# Group_02.net
KiCad netlist of a schematic drawn in EAGLE
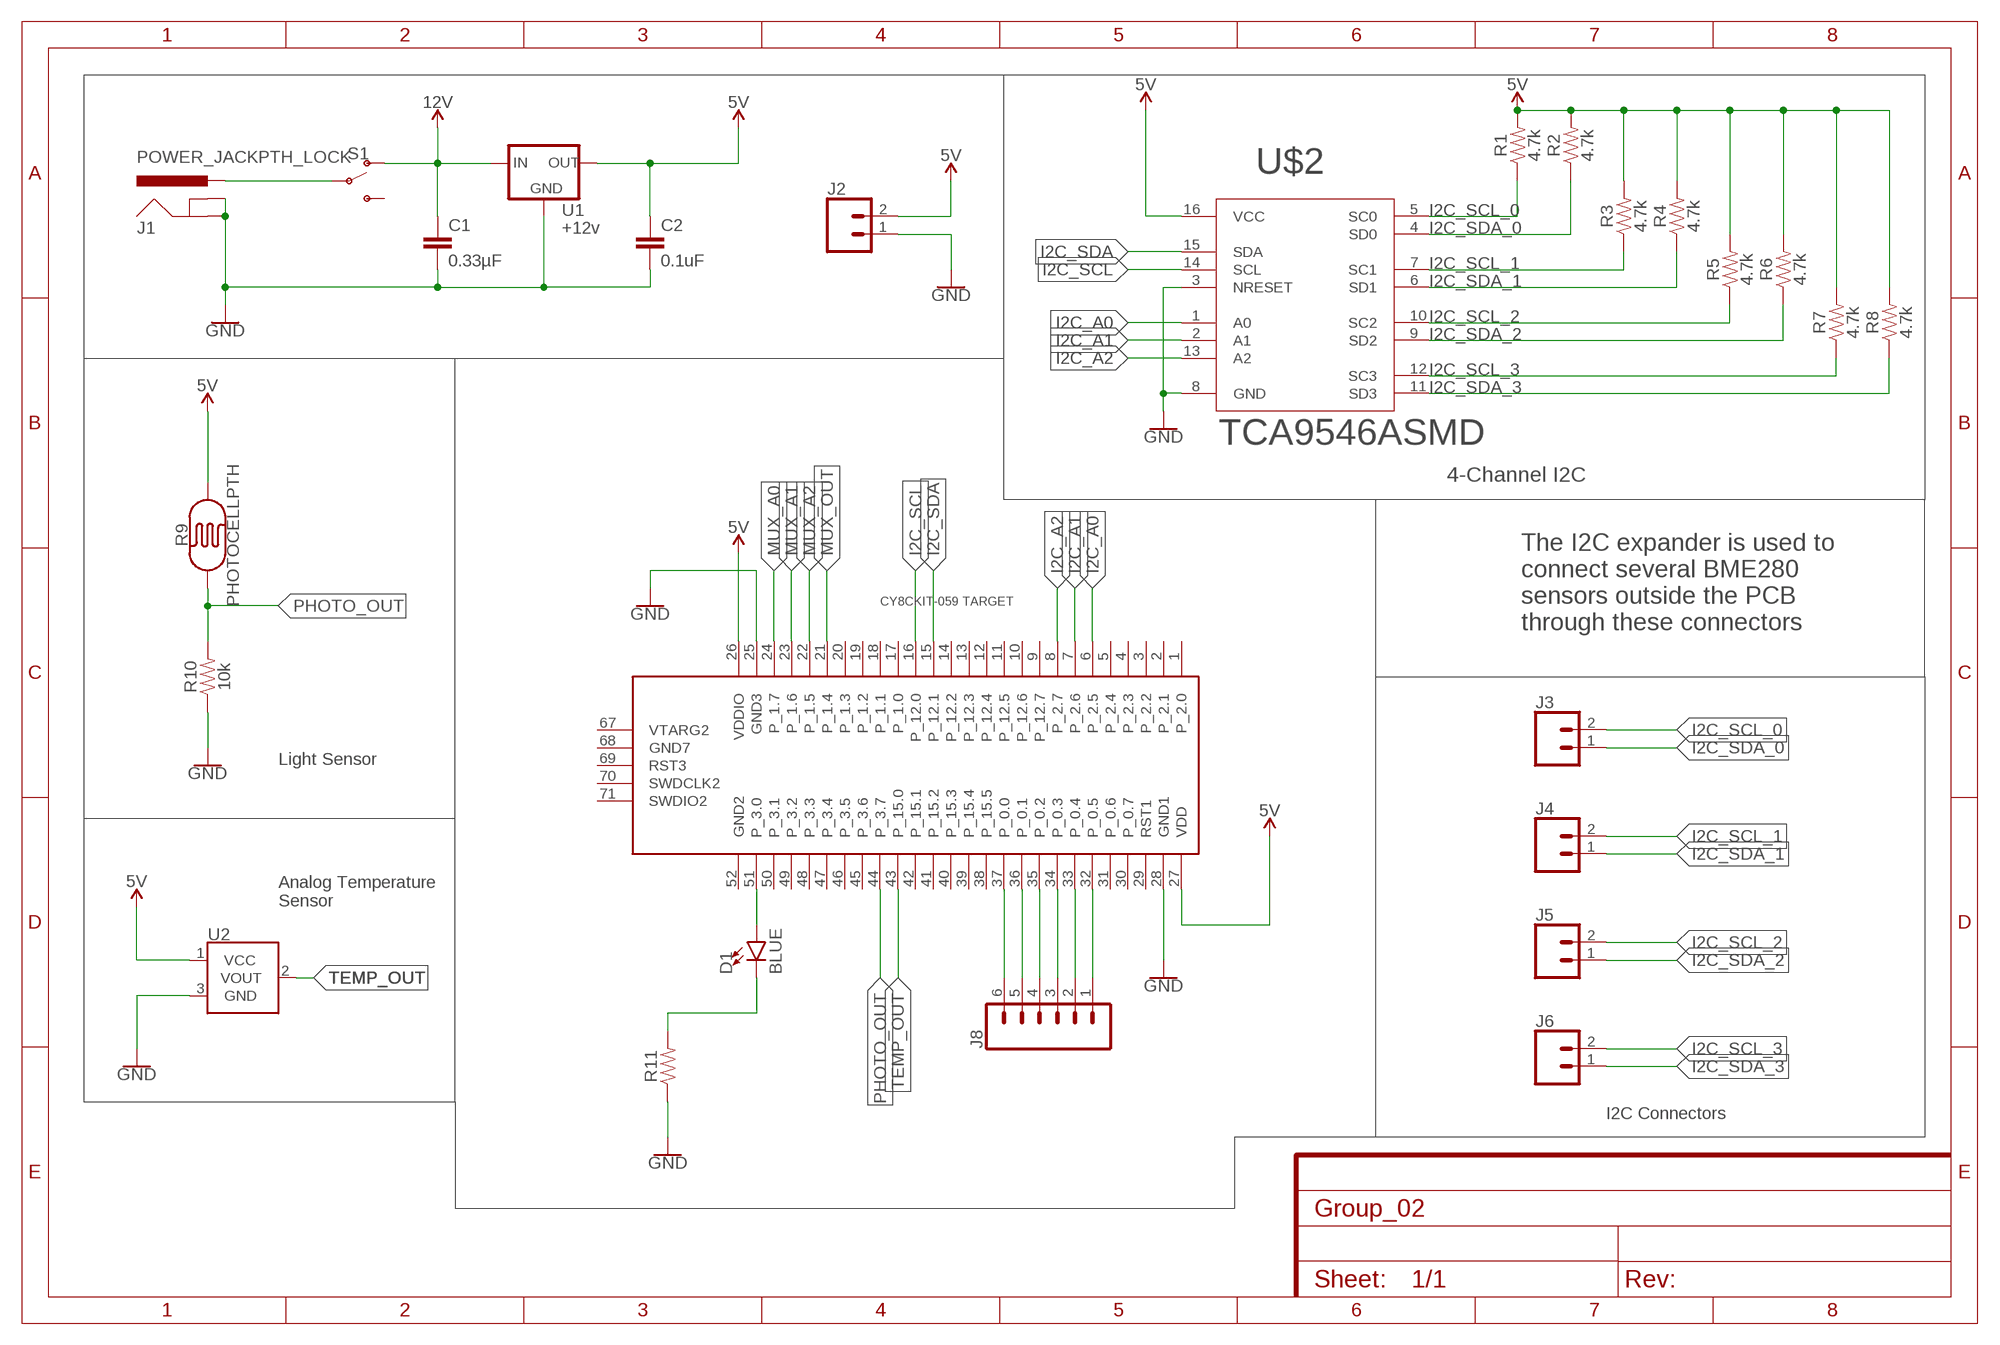
[diagram p0: schematic, sheet 1, part 1 of 2]
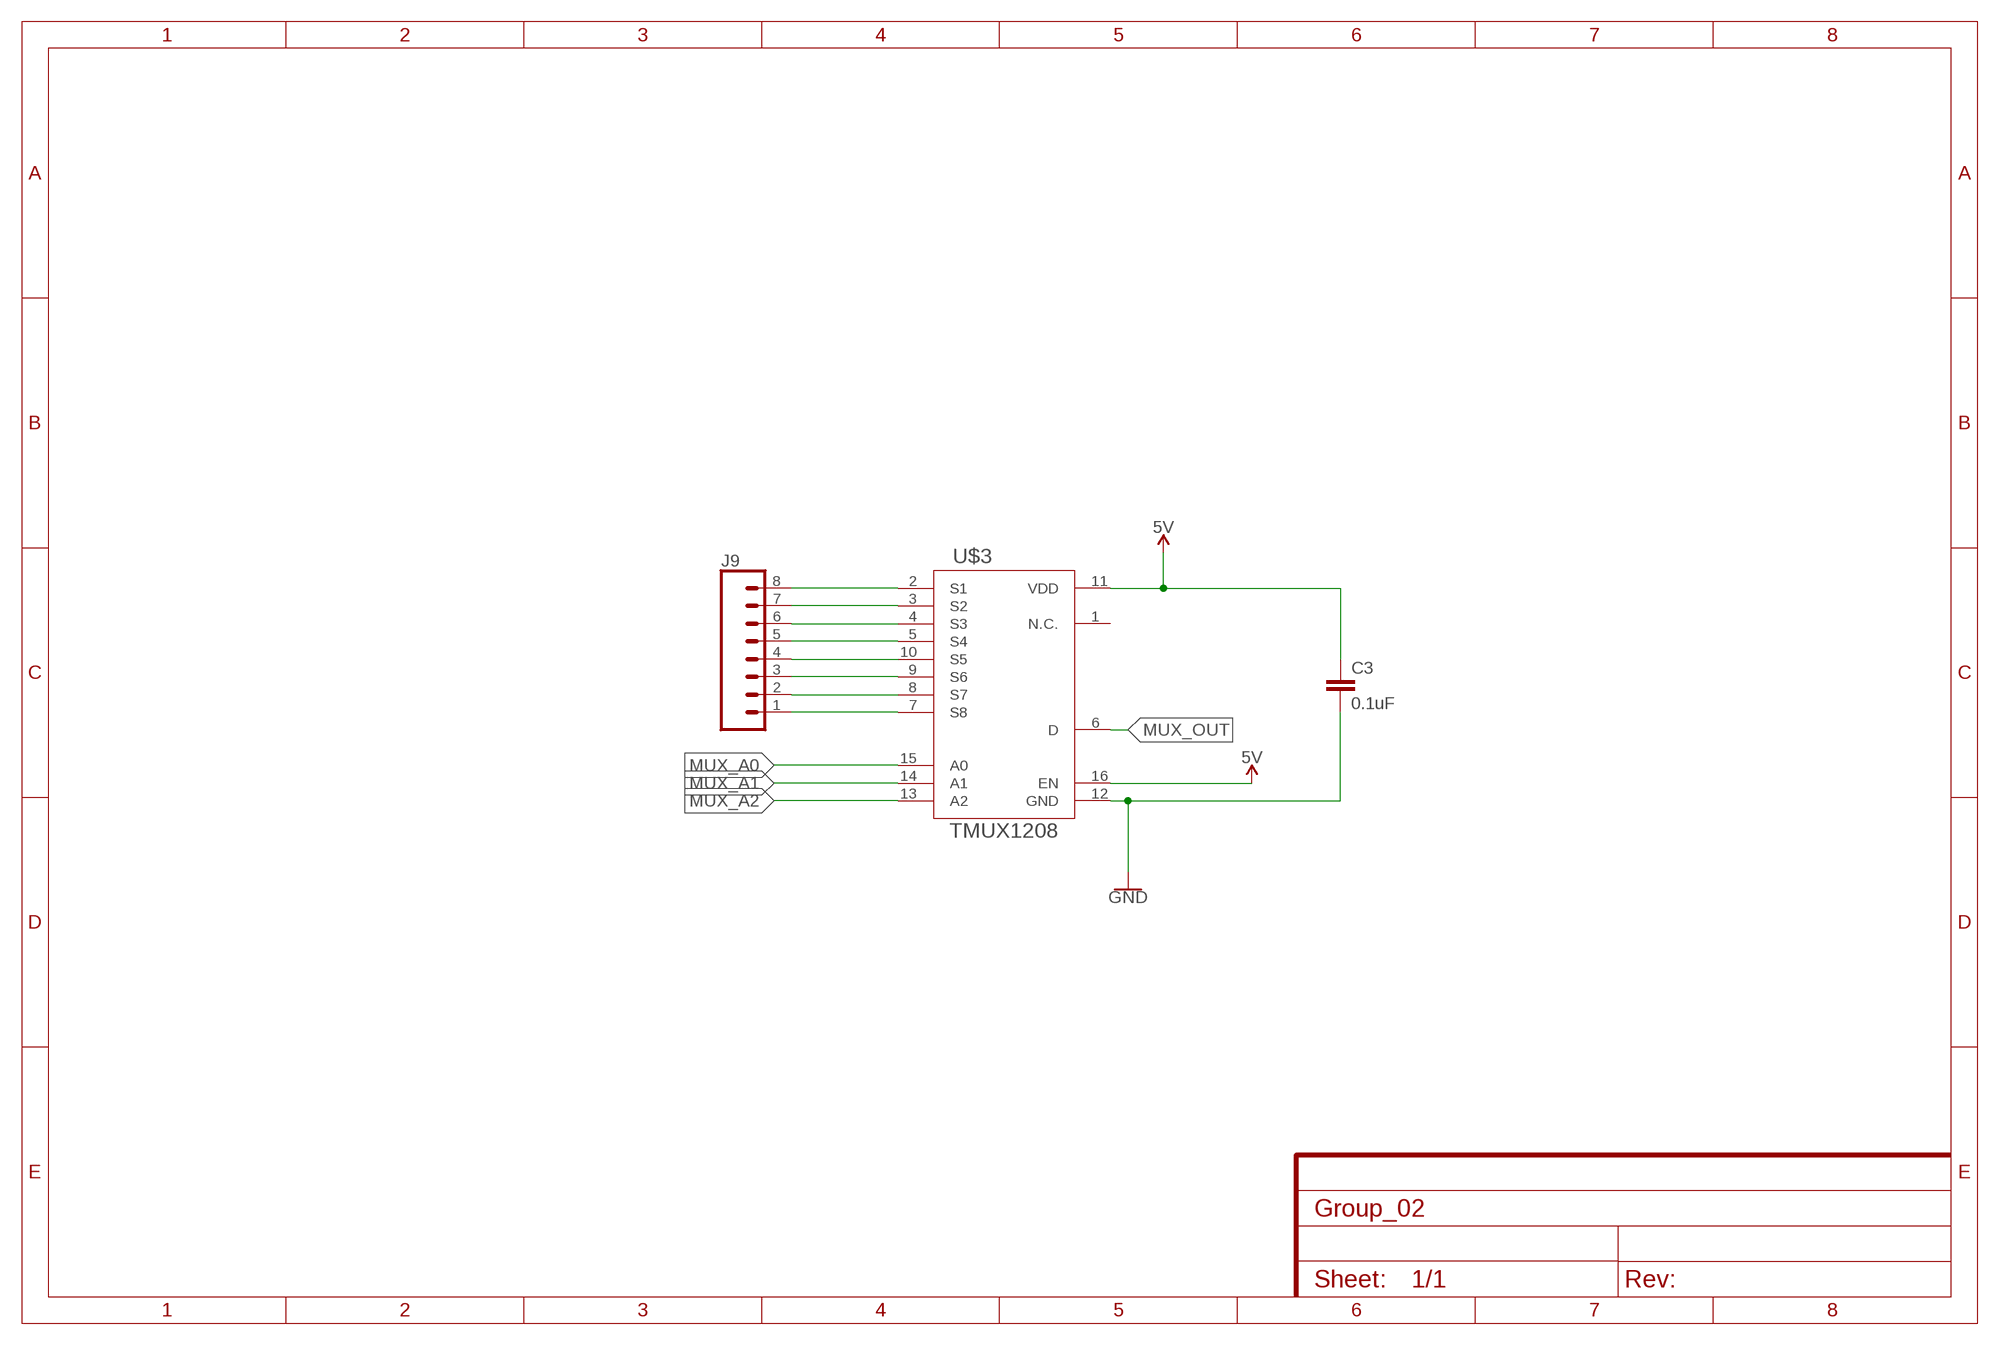
[diagram p1: schematic, sheet 1, part 2 of 2]

(export (version "E")
  (design (tool "Eeschema 10.0.6"))
  (components
    (comp (ref "C1")
      (value "0.33µF")
      (footprint "eagle-import:0805")
      (libsource (lib "eagle-import") (part "0.33UF/330NF-0805-50V-10%"))
    )
    (comp (ref "C2")
      (value "0.1uF")
      (footprint "eagle-import:CAP-PTH-SMALL-KIT")
      (libsource (lib "eagle-import") (part "0.1UF-KIT-EZ-50V-20%"))
    )
    (comp (ref "C3")
      (value "0.1uF")
      (footprint "eagle-import:CAP-PTH-SMALL-KIT")
      (libsource (lib "eagle-import") (part "0.1UF-KIT-EZ-50V-20%"))
    )
    (comp (ref "D1")
      (value "BLUE")
      (footprint "eagle-import:LED-1206")
      (libsource (lib "eagle-import") (part "LED-BLUE1206"))
    )
    (comp (ref "J1")
      (value "POWER_JACKPTH_LOCK")
      (footprint "eagle-import:POWER_JACK_PTH_LOCK")
      (libsource (lib "eagle-import") (part "POWER_JACKPTH_LOCK"))
    )
    (comp (ref "J2")
      (value "CONN_02")
      (footprint "eagle-import:1X02")
      (libsource (lib "eagle-import") (part "CONN_02"))
    )
    (comp (ref "J3")
      (value "CONN_02")
      (footprint "eagle-import:1X02")
      (libsource (lib "eagle-import") (part "CONN_02"))
    )
    (comp (ref "J4")
      (value "CONN_02")
      (footprint "eagle-import:1X02")
      (libsource (lib "eagle-import") (part "CONN_02"))
    )
    (comp (ref "J5")
      (value "CONN_02")
      (footprint "eagle-import:1X02")
      (libsource (lib "eagle-import") (part "CONN_02"))
    )
    (comp (ref "J6")
      (value "CONN_02")
      (footprint "eagle-import:1X02")
      (libsource (lib "eagle-import") (part "CONN_02"))
    )
    (comp (ref "J8")
      (value "CONN_06LOCK")
      (footprint "eagle-import:1X06_LOCK")
      (libsource (lib "eagle-import") (part "CONN_06LOCK"))
    )
    (comp (ref "J9")
      (value "CONN_08LOCK")
      (footprint "eagle-import:1X08_LOCK")
      (libsource (lib "eagle-import") (part "CONN_08LOCK"))
    )
    (comp (ref "R1")
      (value "4.7k")
      (footprint "eagle-import:0603")
      (libsource (lib "eagle-import") (part "4.7KOHM-0603-1/10W-1%"))
    )
    (comp (ref "R2")
      (value "4.7k")
      (footprint "eagle-import:0603")
      (libsource (lib "eagle-import") (part "4.7KOHM-0603-1/10W-1%"))
    )
    (comp (ref "R3")
      (value "4.7k")
      (footprint "eagle-import:0603")
      (libsource (lib "eagle-import") (part "4.7KOHM-0603-1/10W-1%"))
    )
    (comp (ref "R4")
      (value "4.7k")
      (footprint "eagle-import:0603")
      (libsource (lib "eagle-import") (part "4.7KOHM-0603-1/10W-1%"))
    )
    (comp (ref "R5")
      (value "4.7k")
      (footprint "eagle-import:0603")
      (libsource (lib "eagle-import") (part "4.7KOHM-0603-1/10W-1%"))
    )
    (comp (ref "R6")
      (value "4.7k")
      (footprint "eagle-import:0603")
      (libsource (lib "eagle-import") (part "4.7KOHM-0603-1/10W-1%"))
    )
    (comp (ref "R7")
      (value "4.7k")
      (footprint "eagle-import:0603")
      (libsource (lib "eagle-import") (part "4.7KOHM-0603-1/10W-1%"))
    )
    (comp (ref "R8")
      (value "4.7k")
      (footprint "eagle-import:0603")
      (libsource (lib "eagle-import") (part "4.7KOHM-0603-1/10W-1%"))
    )
    (comp (ref "R9")
      (value "PHOTOCELLPTH")
      (footprint "eagle-import:PHOTOCELL")
      (libsource (lib "eagle-import") (part "PHOTOCELLPTH"))
    )
    (comp (ref "R10")
      (value "10k")
      (footprint "eagle-import:0603")
      (libsource (lib "eagle-import") (part "10KOHM-0603-1/10W-1%"))
    )
    (comp (ref "R11")
      (value "RESISTORAXIAL-0.3")
      (footprint "eagle-import:AXIAL-0.3")
      (libsource (lib "eagle-import") (part "RESISTORAXIAL-0.3"))
    )
    (comp (ref "S1")
      (value "SWITCH-SPDT-PTH-11.6X4.0MM")
      (footprint "eagle-import:SWITCH_SPDT_PTH_11.6X4.0MM")
      (libsource (lib "eagle-import") (part "SWITCH-SPDT-PTH-11.6X4.0MM"))
    )
    (comp (ref "U$1")
      (value "CY8CKIT-059_TARGET")
      (footprint "eagle-import:CY8CKIT-059_TARGET")
      (libsource (lib "eagle-import") (part "CY8CKIT-059_TARGET"))
    )
    (comp (ref "U$2")
      (value "TCA9546ASMD")
      (footprint "eagle-import:TSSOP-16")
      (libsource (lib "eagle-import") (part "TCA9546ASMD"))
    )
    (comp (ref "U$3")
      (value "TMUX1208")
      (footprint "eagle-import:QFN-16")
      (libsource (lib "eagle-import") (part "TMUX1208"))
    )
    (comp (ref "U1")
      (value "+12v")
      (footprint "eagle-import:TO-252")
      (libsource (lib "eagle-import") (part "V_REG_78XX7812"))
    )
    (comp (ref "U2")
      (value "TMP36GT9")
      (footprint "eagle-import:TO-92")
      (libsource (lib "eagle-import") (part "TMP36GT9"))
    )
  )
  (nets
    (net (code "1") (name "5V") (class "Default")
      (node (ref "C2") (pin "1") (pinfunction "1_1") (pintype "passive"))
      (node (ref "C3") (pin "1") (pinfunction "1_1") (pintype "passive"))
      (node (ref "J2") (pin "2") (pinfunction "2_2") (pintype "passive"))
      (node (ref "R1") (pin "2") (pinfunction "2_2") (pintype "passive"))
      (node (ref "R2") (pin "2") (pinfunction "2_2") (pintype "passive"))
      (node (ref "R3") (pin "2") (pinfunction "2_2") (pintype "passive"))
      (node (ref "R4") (pin "2") (pinfunction "2_2") (pintype "passive"))
      (node (ref "R5") (pin "2") (pinfunction "2_2") (pintype "passive"))
      (node (ref "R6") (pin "2") (pinfunction "2_2") (pintype "passive"))
      (node (ref "R7") (pin "2") (pinfunction "2_2") (pintype "passive"))
      (node (ref "R8") (pin "2") (pinfunction "2_2") (pintype "passive"))
      (node (ref "R9") (pin "2") (pinfunction "P$2_2") (pintype "bidirectional"))
      (node (ref "U$1") (pin "26") (pinfunction "VDDIO_26") (pintype "bidirectional"))
      (node (ref "U$1") (pin "27") (pinfunction "VDD_27") (pintype "bidirectional"))
      (node (ref "U$2") (pin "16") (pinfunction "VCC_16") (pintype "bidirectional"))
      (node (ref "U$3") (pin "11") (pinfunction "VDD_11") (pintype "bidirectional"))
      (node (ref "U$3") (pin "16") (pinfunction "EN_16") (pintype "bidirectional"))
      (node (ref "U1") (pin "2") (pinfunction "OUT_2") (pintype "passive"))
      (node (ref "U2") (pin "1") (pinfunction "VCC_1") (pintype "bidirectional"))
    )
    (net (code "2") (name "12V") (class "Default")
      (node (ref "C1") (pin "1") (pinfunction "1_1") (pintype "passive"))
      (node (ref "S1") (pin "1") (pinfunction "O_1") (pintype "passive"))
      (node (ref "U1") (pin "1") (pinfunction "IN_1") (pintype "input"))
    )
    (net (code "3") (name "GND") (class "Default")
      (node (ref "C1") (pin "2") (pinfunction "2_2") (pintype "passive"))
      (node (ref "C2") (pin "2") (pinfunction "2_2") (pintype "passive"))
      (node (ref "C3") (pin "2") (pinfunction "2_2") (pintype "passive"))
      (node (ref "J1") (pin "GND") (pinfunction "GND_GND") (pintype "bidirectional"))
      (node (ref "J1") (pin "GNDBREAK") (pinfunction "GNDBREAK_GNDBREAK") (pintype "bidirectional"))
      (node (ref "J2") (pin "1") (pinfunction "1_1") (pintype "passive"))
      (node (ref "R10") (pin "1") (pinfunction "1_1") (pintype "passive"))
      (node (ref "R11") (pin "P$1") (pinfunction "1_P$1") (pintype "passive"))
      (node (ref "U$1") (pin "25") (pinfunction "GND3_25") (pintype "bidirectional"))
      (node (ref "U$1") (pin "28") (pinfunction "GND1_28") (pintype "bidirectional"))
      (node (ref "U$2") (pin "3") (pinfunction "NRESET_3") (pintype "bidirectional"))
      (node (ref "U$2") (pin "8") (pinfunction "GND_8") (pintype "bidirectional"))
      (node (ref "U$3") (pin "12") (pinfunction "GND_12") (pintype "bidirectional"))
      (node (ref "U1") (pin "3") (pinfunction "GND_3") (pintype "input"))
      (node (ref "U2") (pin "3") (pinfunction "GND_3") (pintype "bidirectional"))
    )
    (net (code "4") (name "I2C_A0") (class "Default")
      (node (ref "U$1") (pin "6") (pinfunction "P_2.5_6") (pintype "bidirectional"))
      (node (ref "U$2") (pin "1") (pinfunction "A0_1") (pintype "bidirectional"))
    )
    (net (code "5") (name "I2C_A1") (class "Default")
      (node (ref "U$1") (pin "7") (pinfunction "P_2.6_7") (pintype "bidirectional"))
      (node (ref "U$2") (pin "2") (pinfunction "A1_2") (pintype "bidirectional"))
    )
    (net (code "6") (name "I2C_A2") (class "Default")
      (node (ref "U$1") (pin "8") (pinfunction "P_2.7_8") (pintype "bidirectional"))
      (node (ref "U$2") (pin "13") (pinfunction "A2_13") (pintype "bidirectional"))
    )
    (net (code "7") (name "I2C_SCL") (class "Default")
      (node (ref "U$1") (pin "16") (pinfunction "P_12.0_16") (pintype "bidirectional"))
      (node (ref "U$2") (pin "14") (pinfunction "SCL_14") (pintype "bidirectional"))
    )
    (net (code "8") (name "I2C_SCL_0") (class "Default")
      (node (ref "J3") (pin "2") (pinfunction "2_2") (pintype "passive"))
      (node (ref "R1") (pin "1") (pinfunction "1_1") (pintype "passive"))
      (node (ref "U$2") (pin "5") (pinfunction "SC0_5") (pintype "bidirectional"))
    )
    (net (code "9") (name "I2C_SCL_1") (class "Default")
      (node (ref "J4") (pin "2") (pinfunction "2_2") (pintype "passive"))
      (node (ref "R3") (pin "1") (pinfunction "1_1") (pintype "passive"))
      (node (ref "U$2") (pin "7") (pinfunction "SC1_7") (pintype "bidirectional"))
    )
    (net (code "10") (name "I2C_SCL_2") (class "Default")
      (node (ref "J5") (pin "2") (pinfunction "2_2") (pintype "passive"))
      (node (ref "R5") (pin "1") (pinfunction "1_1") (pintype "passive"))
      (node (ref "U$2") (pin "10") (pinfunction "SC2_10") (pintype "bidirectional"))
    )
    (net (code "11") (name "I2C_SCL_3") (class "Default")
      (node (ref "J6") (pin "2") (pinfunction "2_2") (pintype "passive"))
      (node (ref "R7") (pin "1") (pinfunction "1_1") (pintype "passive"))
      (node (ref "U$2") (pin "12") (pinfunction "SC3_12") (pintype "bidirectional"))
    )
    (net (code "12") (name "I2C_SDA") (class "Default")
      (node (ref "U$1") (pin "15") (pinfunction "P_12.1_15") (pintype "bidirectional"))
      (node (ref "U$2") (pin "15") (pinfunction "SDA_15") (pintype "bidirectional"))
    )
    (net (code "13") (name "I2C_SDA_0") (class "Default")
      (node (ref "J3") (pin "1") (pinfunction "1_1") (pintype "passive"))
      (node (ref "R2") (pin "1") (pinfunction "1_1") (pintype "passive"))
      (node (ref "U$2") (pin "4") (pinfunction "SD0_4") (pintype "bidirectional"))
    )
    (net (code "14") (name "I2C_SDA_1") (class "Default")
      (node (ref "J4") (pin "1") (pinfunction "1_1") (pintype "passive"))
      (node (ref "R4") (pin "1") (pinfunction "1_1") (pintype "passive"))
      (node (ref "U$2") (pin "6") (pinfunction "SD1_6") (pintype "bidirectional"))
    )
    (net (code "15") (name "I2C_SDA_2") (class "Default")
      (node (ref "J5") (pin "1") (pinfunction "1_1") (pintype "passive"))
      (node (ref "R6") (pin "1") (pinfunction "1_1") (pintype "passive"))
      (node (ref "U$2") (pin "9") (pinfunction "SD2_9") (pintype "bidirectional"))
    )
    (net (code "16") (name "I2C_SDA_3") (class "Default")
      (node (ref "J6") (pin "1") (pinfunction "1_1") (pintype "passive"))
      (node (ref "R8") (pin "1") (pinfunction "1_1") (pintype "passive"))
      (node (ref "U$2") (pin "11") (pinfunction "SD3_11") (pintype "bidirectional"))
    )
    (net (code "17") (name "MUX_A0") (class "Default")
      (node (ref "U$1") (pin "24") (pinfunction "P_1.7_24") (pintype "bidirectional"))
      (node (ref "U$3") (pin "15") (pinfunction "A0_15") (pintype "bidirectional"))
    )
    (net (code "18") (name "MUX_A1") (class "Default")
      (node (ref "U$1") (pin "23") (pinfunction "P_1.6_23") (pintype "bidirectional"))
      (node (ref "U$3") (pin "14") (pinfunction "A1_14") (pintype "bidirectional"))
    )
    (net (code "19") (name "MUX_A2") (class "Default")
      (node (ref "U$1") (pin "22") (pinfunction "P_1.5_22") (pintype "bidirectional"))
      (node (ref "U$3") (pin "13") (pinfunction "A2_13") (pintype "bidirectional"))
    )
    (net (code "20") (name "MUX_OUT") (class "Default")
      (node (ref "U$1") (pin "21") (pinfunction "P_1.4_21") (pintype "bidirectional"))
      (node (ref "U$3") (pin "6") (pinfunction "D_6") (pintype "bidirectional"))
    )
    (net (code "21") (name "Net-(R11-2)") (class "Default")
      (node (ref "D1") (pin "C") (pinfunction "C_C") (pintype "passive"))
      (node (ref "R11") (pin "P$2") (pinfunction "2_P$2") (pintype "passive"))
    )
    (net (code "22") (name "Net-(S1-P)") (class "Default")
      (node (ref "J1") (pin "PWR") (pinfunction "PWR_PWR") (pintype "bidirectional"))
      (node (ref "S1") (pin "2") (pinfunction "P_2") (pintype "passive"))
    )
    (net (code "23") (name "Net-(U$1-P_0.0)") (class "Default")
      (node (ref "J8") (pin "6") (pinfunction "6_6") (pintype "passive"))
      (node (ref "U$1") (pin "37") (pinfunction "P_0.0_37") (pintype "bidirectional"))
    )
    (net (code "24") (name "Net-(U$1-P_0.1)") (class "Default")
      (node (ref "J8") (pin "5") (pinfunction "5_5") (pintype "passive"))
      (node (ref "U$1") (pin "36") (pinfunction "P_0.1_36") (pintype "bidirectional"))
    )
    (net (code "25") (name "Net-(U$1-P_0.2)") (class "Default")
      (node (ref "J8") (pin "4") (pinfunction "4_4") (pintype "passive"))
      (node (ref "U$1") (pin "35") (pinfunction "P_0.2_35") (pintype "bidirectional"))
    )
    (net (code "26") (name "Net-(U$1-P_0.3)") (class "Default")
      (node (ref "J8") (pin "3") (pinfunction "3_3") (pintype "passive"))
      (node (ref "U$1") (pin "34") (pinfunction "P_0.3_34") (pintype "bidirectional"))
    )
    (net (code "27") (name "Net-(U$1-P_0.4)") (class "Default")
      (node (ref "J8") (pin "2") (pinfunction "2_2") (pintype "passive"))
      (node (ref "U$1") (pin "33") (pinfunction "P_0.4_33") (pintype "bidirectional"))
    )
    (net (code "28") (name "Net-(U$1-P_0.5)") (class "Default")
      (node (ref "J8") (pin "1") (pinfunction "1_1") (pintype "passive"))
      (node (ref "U$1") (pin "32") (pinfunction "P_0.5_32") (pintype "bidirectional"))
    )
    (net (code "29") (name "Net-(U$1-P_3.0)") (class "Default")
      (node (ref "D1") (pin "A") (pinfunction "A_A") (pintype "passive"))
      (node (ref "U$1") (pin "51") (pinfunction "P_3.0_51") (pintype "bidirectional"))
    )
    (net (code "30") (name "Net-(U$3-S1)") (class "Default")
      (node (ref "J9") (pin "8") (pinfunction "8_8") (pintype "passive"))
      (node (ref "U$3") (pin "2") (pinfunction "S1_2") (pintype "bidirectional"))
    )
    (net (code "31") (name "Net-(U$3-S2)") (class "Default")
      (node (ref "J9") (pin "7") (pinfunction "7_7") (pintype "passive"))
      (node (ref "U$3") (pin "3") (pinfunction "S2_3") (pintype "bidirectional"))
    )
    (net (code "32") (name "Net-(U$3-S3)") (class "Default")
      (node (ref "J9") (pin "6") (pinfunction "6_6") (pintype "passive"))
      (node (ref "U$3") (pin "4") (pinfunction "S3_4") (pintype "bidirectional"))
    )
    (net (code "33") (name "Net-(U$3-S4)") (class "Default")
      (node (ref "J9") (pin "5") (pinfunction "5_5") (pintype "passive"))
      (node (ref "U$3") (pin "5") (pinfunction "S4_5") (pintype "bidirectional"))
    )
    (net (code "34") (name "Net-(U$3-S5)") (class "Default")
      (node (ref "J9") (pin "4") (pinfunction "4_4") (pintype "passive"))
      (node (ref "U$3") (pin "10") (pinfunction "S5_10") (pintype "bidirectional"))
    )
    (net (code "35") (name "Net-(U$3-S6)") (class "Default")
      (node (ref "J9") (pin "3") (pinfunction "3_3") (pintype "passive"))
      (node (ref "U$3") (pin "9") (pinfunction "S6_9") (pintype "bidirectional"))
    )
    (net (code "36") (name "Net-(U$3-S7)") (class "Default")
      (node (ref "J9") (pin "2") (pinfunction "2_2") (pintype "passive"))
      (node (ref "U$3") (pin "8") (pinfunction "S7_8") (pintype "bidirectional"))
    )
    (net (code "37") (name "Net-(U$3-S8)") (class "Default")
      (node (ref "J9") (pin "1") (pinfunction "1_1") (pintype "passive"))
      (node (ref "U$3") (pin "7") (pinfunction "S8_7") (pintype "bidirectional"))
    )
    (net (code "38") (name "PHOTO_OUT") (class "Default")
      (node (ref "R10") (pin "2") (pinfunction "2_2") (pintype "passive"))
      (node (ref "R9") (pin "1") (pinfunction "P$1_1") (pintype "bidirectional"))
      (node (ref "U$1") (pin "44") (pinfunction "P_3.7_44") (pintype "bidirectional"))
    )
    (net (code "39") (name "TEMP_OUT") (class "Default")
      (node (ref "U$1") (pin "43") (pinfunction "P_15.0_43") (pintype "bidirectional"))
      (node (ref "U2") (pin "2") (pinfunction "VOUT_2") (pintype "bidirectional"))
    )
    (net (code "40") (name "unconnected-(S1-S-Pad3)") (class "Default")
      (node (ref "S1") (pin "3") (pinfunction "S_3") (pintype "passive"))
    )
    (net (code "41") (name "unconnected-(U$1-GND2-Pad52)") (class "Default")
      (node (ref "U$1") (pin "52") (pinfunction "GND2_52") (pintype "bidirectional"))
    )
    (net (code "42") (name "unconnected-(U$1-GND7-Pad68)") (class "Default")
      (node (ref "U$1") (pin "68") (pinfunction "GND7_68") (pintype "bidirectional"))
    )
    (net (code "43") (name "unconnected-(U$1-P_0.6-Pad31)") (class "Default")
      (node (ref "U$1") (pin "31") (pinfunction "P_0.6_31") (pintype "bidirectional"))
    )
    (net (code "44") (name "unconnected-(U$1-P_0.7-Pad30)") (class "Default")
      (node (ref "U$1") (pin "30") (pinfunction "P_0.7_30") (pintype "bidirectional"))
    )
    (net (code "45") (name "unconnected-(U$1-P_1.0-Pad17)") (class "Default")
      (node (ref "U$1") (pin "17") (pinfunction "P_1.0_17") (pintype "bidirectional"))
    )
    (net (code "46") (name "unconnected-(U$1-P_1.1-Pad18)") (class "Default")
      (node (ref "U$1") (pin "18") (pinfunction "P_1.1_18") (pintype "bidirectional"))
    )
    (net (code "47") (name "unconnected-(U$1-P_1.2-Pad19)") (class "Default")
      (node (ref "U$1") (pin "19") (pinfunction "P_1.2_19") (pintype "bidirectional"))
    )
    (net (code "48") (name "unconnected-(U$1-P_1.3-Pad20)") (class "Default")
      (node (ref "U$1") (pin "20") (pinfunction "P_1.3_20") (pintype "bidirectional"))
    )
    (net (code "49") (name "unconnected-(U$1-P_2.0-Pad1)") (class "Default")
      (node (ref "U$1") (pin "1") (pinfunction "P_2.0_1") (pintype "bidirectional"))
    )
    (net (code "50") (name "unconnected-(U$1-P_2.1-Pad2)") (class "Default")
      (node (ref "U$1") (pin "2") (pinfunction "P_2.1_2") (pintype "bidirectional"))
    )
    (net (code "51") (name "unconnected-(U$1-P_2.2-Pad3)") (class "Default")
      (node (ref "U$1") (pin "3") (pinfunction "P_2.2_3") (pintype "bidirectional"))
    )
    (net (code "52") (name "unconnected-(U$1-P_2.3-Pad4)") (class "Default")
      (node (ref "U$1") (pin "4") (pinfunction "P_2.3_4") (pintype "bidirectional"))
    )
    (net (code "53") (name "unconnected-(U$1-P_2.4-Pad5)") (class "Default")
      (node (ref "U$1") (pin "5") (pinfunction "P_2.4_5") (pintype "bidirectional"))
    )
    (net (code "54") (name "unconnected-(U$1-P_3.1-Pad50)") (class "Default")
      (node (ref "U$1") (pin "50") (pinfunction "P_3.1_50") (pintype "bidirectional"))
    )
    (net (code "55") (name "unconnected-(U$1-P_3.2-Pad49)") (class "Default")
      (node (ref "U$1") (pin "49") (pinfunction "P_3.2_49") (pintype "bidirectional"))
    )
    (net (code "56") (name "unconnected-(U$1-P_3.3-Pad48)") (class "Default")
      (node (ref "U$1") (pin "48") (pinfunction "P_3.3_48") (pintype "bidirectional"))
    )
    (net (code "57") (name "unconnected-(U$1-P_3.4-Pad47)") (class "Default")
      (node (ref "U$1") (pin "47") (pinfunction "P_3.4_47") (pintype "bidirectional"))
    )
    (net (code "58") (name "unconnected-(U$1-P_3.5-Pad46)") (class "Default")
      (node (ref "U$1") (pin "46") (pinfunction "P_3.5_46") (pintype "bidirectional"))
    )
    (net (code "59") (name "unconnected-(U$1-P_3.6-Pad45)") (class "Default")
      (node (ref "U$1") (pin "45") (pinfunction "P_3.6_45") (pintype "bidirectional"))
    )
    (net (code "60") (name "unconnected-(U$1-P_12.2-Pad14)") (class "Default")
      (node (ref "U$1") (pin "14") (pinfunction "P_12.2_14") (pintype "bidirectional"))
    )
    (net (code "61") (name "unconnected-(U$1-P_12.3-Pad13)") (class "Default")
      (node (ref "U$1") (pin "13") (pinfunction "P_12.3_13") (pintype "bidirectional"))
    )
    (net (code "62") (name "unconnected-(U$1-P_12.4-Pad12)") (class "Default")
      (node (ref "U$1") (pin "12") (pinfunction "P_12.4_12") (pintype "bidirectional"))
    )
    (net (code "63") (name "unconnected-(U$1-P_12.5-Pad11)") (class "Default")
      (node (ref "U$1") (pin "11") (pinfunction "P_12.5_11") (pintype "bidirectional"))
    )
    (net (code "64") (name "unconnected-(U$1-P_12.6-Pad10)") (class "Default")
      (node (ref "U$1") (pin "10") (pinfunction "P_12.6_10") (pintype "bidirectional"))
    )
    (net (code "65") (name "unconnected-(U$1-P_12.7-Pad9)") (class "Default")
      (node (ref "U$1") (pin "9") (pinfunction "P_12.7_9") (pintype "bidirectional"))
    )
    (net (code "66") (name "unconnected-(U$1-P_15.1-Pad42)") (class "Default")
      (node (ref "U$1") (pin "42") (pinfunction "P_15.1_42") (pintype "bidirectional"))
    )
    (net (code "67") (name "unconnected-(U$1-P_15.2-Pad41)") (class "Default")
      (node (ref "U$1") (pin "41") (pinfunction "P_15.2_41") (pintype "bidirectional"))
    )
    (net (code "68") (name "unconnected-(U$1-P_15.3-Pad40)") (class "Default")
      (node (ref "U$1") (pin "40") (pinfunction "P_15.3_40") (pintype "bidirectional"))
    )
    (net (code "69") (name "unconnected-(U$1-P_15.4-Pad39)") (class "Default")
      (node (ref "U$1") (pin "39") (pinfunction "P_15.4_39") (pintype "bidirectional"))
    )
    (net (code "70") (name "unconnected-(U$1-P_15.5-Pad38)") (class "Default")
      (node (ref "U$1") (pin "38") (pinfunction "P_15.5_38") (pintype "bidirectional"))
    )
    (net (code "71") (name "unconnected-(U$1-RST1-Pad29)") (class "Default")
      (node (ref "U$1") (pin "29") (pinfunction "RST1_29") (pintype "bidirectional"))
    )
    (net (code "72") (name "unconnected-(U$1-RST3-Pad69)") (class "Default")
      (node (ref "U$1") (pin "69") (pinfunction "RST3_69") (pintype "bidirectional"))
    )
    (net (code "73") (name "unconnected-(U$1-SWDCLK2-Pad70)") (class "Default")
      (node (ref "U$1") (pin "70") (pinfunction "SWDCLK2_70") (pintype "bidirectional"))
    )
    (net (code "74") (name "unconnected-(U$1-SWDIO2-Pad71)") (class "Default")
      (node (ref "U$1") (pin "71") (pinfunction "SWDIO2_71") (pintype "bidirectional"))
    )
    (net (code "75") (name "unconnected-(U$1-VTARG2-Pad67)") (class "Default")
      (node (ref "U$1") (pin "67") (pinfunction "VTARG2_67") (pintype "bidirectional"))
    )
    (net (code "76") (name "unconnected-(U$3-N.C.-Pad1)") (class "Default")
      (node (ref "U$3") (pin "1") (pinfunction "N.C._1") (pintype "bidirectional"))
    )
  )
)
